# SCH_STM32_V03_2022-12-15.net
KiCad netlist of a schematic drawn in EasyEDA
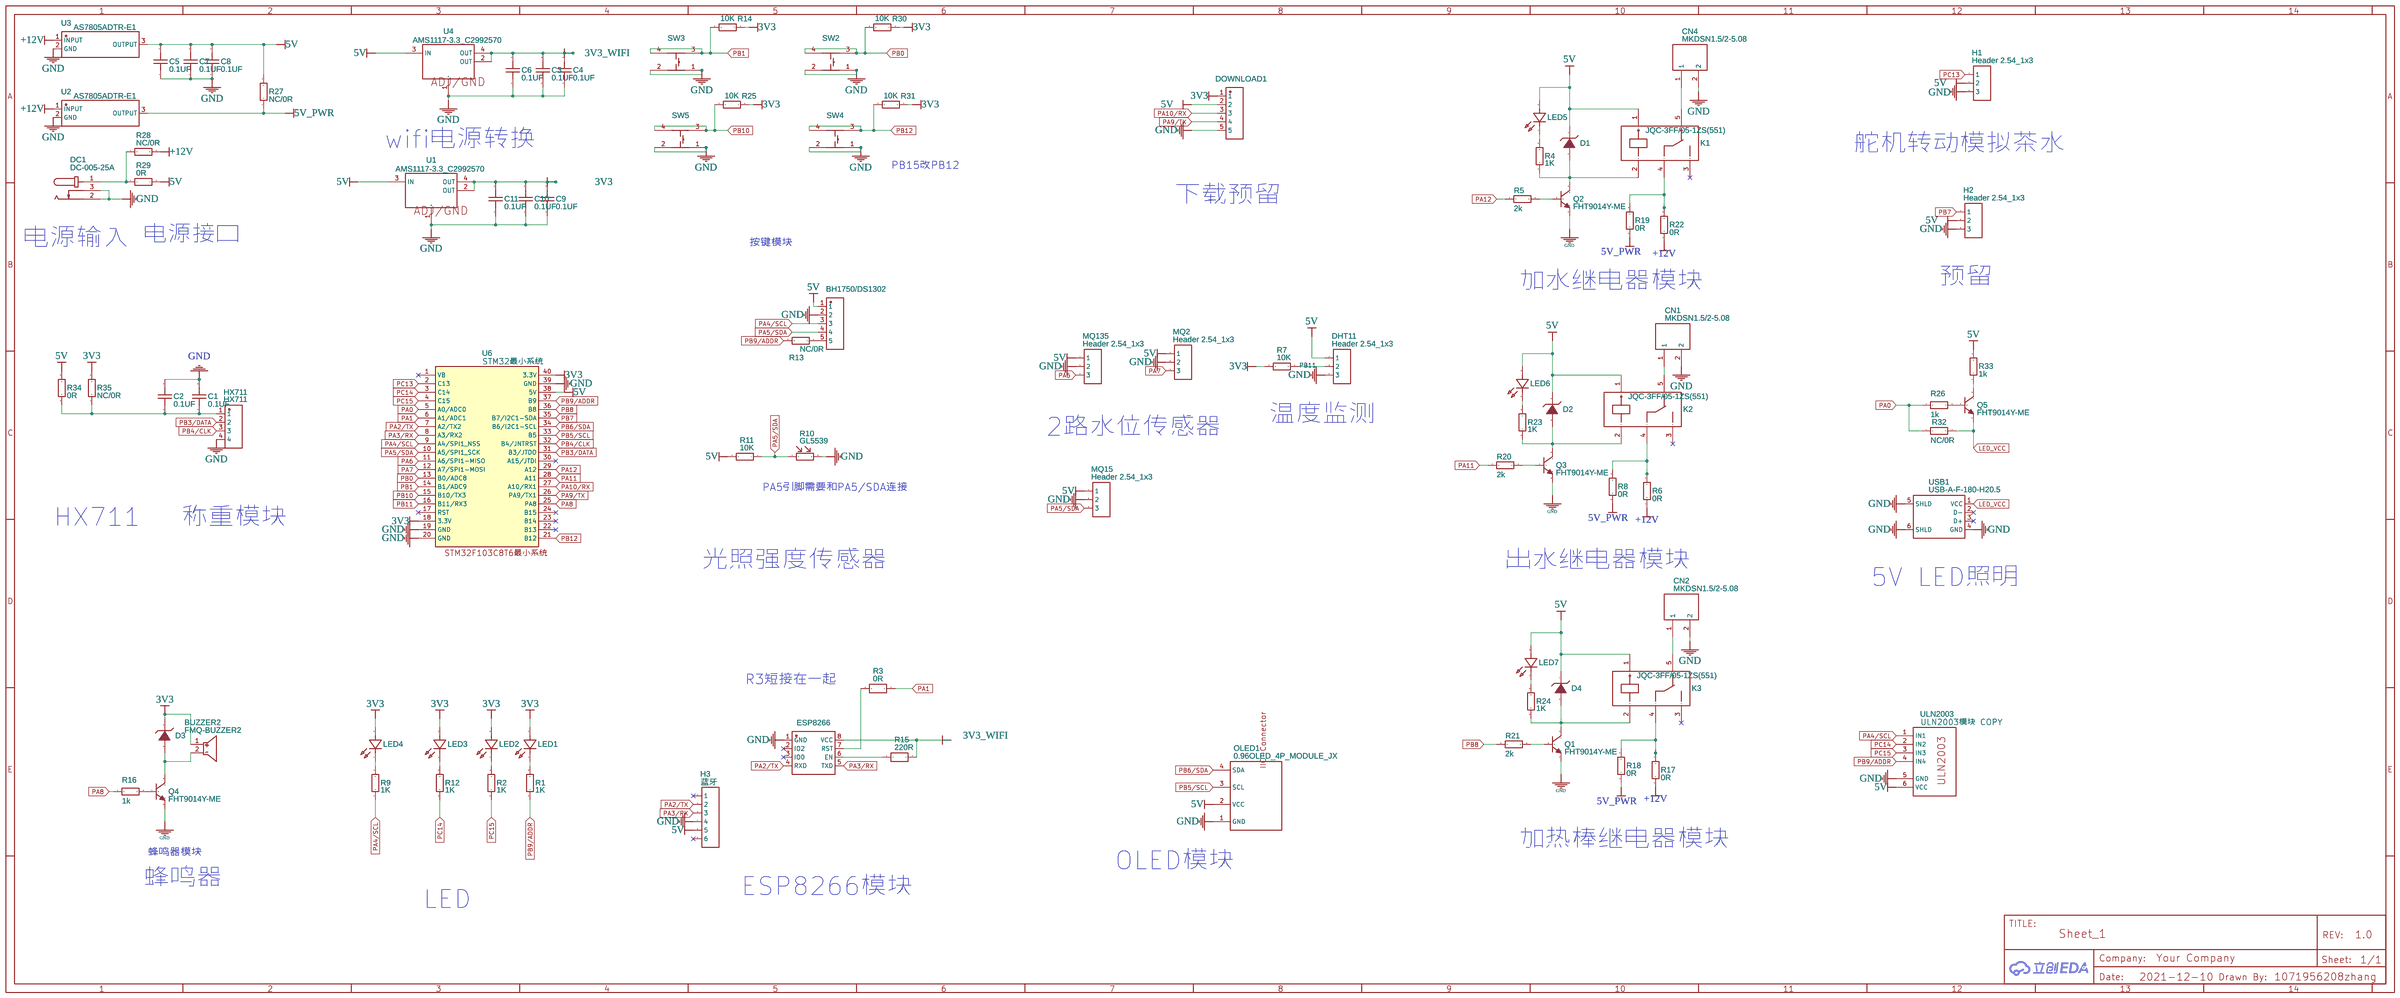
[diagram p0: schematic sheet]

(export (version "E")
  (design (tool "Eeschema 10.0.6"))
  (components
    (comp (ref "BH1750/DS1302")
      (value "Female header　2.54 1*5Ｐ")
      (fields (field (name "BOM_Supplier Part") "C46341"))
      (libsource (lib "") (part "Female header　2.54 1*5Ｐ"))
    )
    (comp (ref "BUZZER2")
      (value "FMQ-BUZZER2")
      (fields (field (name "BOM_Supplier Part") "C9900006103"))
      (libsource (lib "") (part "FMQ-BUZZER2"))
    )
    (comp (ref "C1") (value "0.1UF") (libsource (lib "") (part "C_0603_US")))
    (comp (ref "C2") (value "0.1UF") (libsource (lib "") (part "C_0603_US")))
    (comp (ref "C3") (value "0.1UF") (libsource (lib "") (part "C_0603_US")))
    (comp (ref "C4") (value "0.1UF") (libsource (lib "") (part "C_0603_US")))
    (comp (ref "C5") (value "0.1UF") (libsource (lib "") (part "C_0603_US")))
    (comp (ref "C6") (value "0.1UF") (libsource (lib "") (part "C_0603_US")))
    (comp (ref "C7") (value "0.1UF") (libsource (lib "") (part "C_0603_US")))
    (comp (ref "C8") (value "0.1UF") (libsource (lib "") (part "C_0603_US")))
    (comp (ref "C9") (value "0.1UF") (libsource (lib "") (part "C_0603_US")))
    (comp (ref "C10") (value "0.1UF") (libsource (lib "") (part "C_0603_US")))
    (comp (ref "C11") (value "0.1UF") (libsource (lib "") (part "C_0603_US")))
    (comp (ref "CN1")
      (value "MKDSN1.5/2-5.08")
      (fields (field (name "BOM_Supplier Part") "C91153"))
      (libsource (lib "") (part "MKDSN1.5/2-5.08"))
    )
    (comp (ref "CN2")
      (value "MKDSN1.5/2-5.08")
      (fields (field (name "BOM_Supplier Part") "C91153"))
      (libsource (lib "") (part "MKDSN1.5/2-5.08"))
    )
    (comp (ref "CN4")
      (value "MKDSN1.5/2-5.08")
      (fields (field (name "BOM_Supplier Part") "C91153"))
      (libsource (lib "") (part "MKDSN1.5/2-5.08"))
    )
    (comp (ref "D1")
      (value "1N4734A_C238924")
      (fields (field (name "BOM_Manufacturer Part") "1N4734A") (field (name "BOM_Supplier Part") "C238924"))
      (libsource (lib "") (part "1N4734A_C238924"))
    )
    (comp (ref "D2")
      (value "1N4734A_C238924")
      (fields (field (name "BOM_Manufacturer Part") "1N4734A") (field (name "BOM_Supplier Part") "C238924"))
      (libsource (lib "") (part "1N4734A_C238924"))
    )
    (comp (ref "D3")
      (value "1N4734A_C238924")
      (fields (field (name "BOM_Manufacturer Part") "1N4734A") (field (name "BOM_Supplier Part") "C238924"))
      (libsource (lib "") (part "1N4734A_C238924"))
    )
    (comp (ref "D4")
      (value "1N4734A_C238924")
      (fields (field (name "BOM_Manufacturer Part") "1N4734A") (field (name "BOM_Supplier Part") "C238924"))
      (libsource (lib "") (part "1N4734A_C238924"))
    )
    (comp (ref "DC1")
      (value "DC-005-25A")
      (fields (field (name "BOM_Supplier Part") "C136715"))
      (libsource (lib "") (part "DC-005-25A"))
    )
    (comp (ref "DHT11")
      (value "Header 2.54_1x3")
      (fields
        (field (name "BOM_Manufacturer Part") "Header2.54mm 1*3P")
        (field (name "BOM_Supplier Part") "C49257")
      )
      (libsource (lib "") (part "Header-Male-2.54_1x3_2"))
    )
    (comp (ref "DOWNLOAD1")
      (value "Female header　2.54 1*5Ｐ")
      (fields (field (name "BOM_Supplier Part") "C46341"))
      (libsource (lib "") (part "Female header　2.54 1*5Ｐ_1"))
    )
    (comp (ref "ESP8266")
      (value "ESP-01S_C503582")
      (fields (field (name "BOM_Manufacturer Part") "ESP-01S") (field (name "BOM_Supplier Part") "C503582"))
      (libsource (lib "") (part "ESP-01S_C503582"))
    )
    (comp (ref "H1")
      (value "Header 2.54_1x3")
      (fields
        (field (name "BOM_Manufacturer Part") "Header2.54mm 1*3P")
        (field (name "BOM_Supplier Part") "C49257")
      )
      (libsource (lib "") (part "Header-Male-2.54_1x3_1"))
    )
    (comp (ref "H2")
      (value "Header 2.54_1x3")
      (fields
        (field (name "BOM_Manufacturer Part") "Header2.54mm 1*3P")
        (field (name "BOM_Supplier Part") "C49257")
      )
      (libsource (lib "") (part "Header-Male-2.54_1x3_1"))
    )
    (comp (ref "H3")
      (value "蓝牙")
      (fields
        (field (name "BOM_Manufacturer Part") "Header-Male-2.54_1x6")
        (field (name "BOM_Supplier Part") "C37208")
      )
      (libsource (lib "") (part "Header-Male-2.54_1x6"))
    )
    (comp (ref "HX711")
      (value "HX711")
      (fields
        (field (name "BOM_Manufacturer Part") "Female header1*4P")
        (field (name "BOM_Supplier Part") "C66508")
      )
      (libsource (lib "") (part "Female header1*4P"))
    )
    (comp (ref "K1")
      (value "JQC-3FF/05-1ZS(551)")
      (fields (field (name "BOM_Supplier Part") "C9221"))
      (libsource (lib "") (part "JQC-3FF/05-1ZS(551)"))
    )
    (comp (ref "K2")
      (value "JQC-3FF/05-1ZS(551)")
      (fields (field (name "BOM_Supplier Part") "C9221"))
      (libsource (lib "") (part "JQC-3FF/05-1ZS(551)"))
    )
    (comp (ref "K3")
      (value "JQC-3FF/05-1ZS(551)")
      (fields (field (name "BOM_Supplier Part") "C9221"))
      (libsource (lib "") (part "JQC-3FF/05-1ZS(551)"))
    )
    (comp (ref "LED1")
      (value "264-7SURT/S530-A3")
      (fields (field (name "BOM_Supplier Part") "C710207"))
      (libsource (lib "") (part "264-7SURT/S530-A3"))
    )
    (comp (ref "LED2")
      (value "264-7SURT/S530-A3")
      (fields (field (name "BOM_Supplier Part") "C710207"))
      (libsource (lib "") (part "264-7SURT/S530-A3"))
    )
    (comp (ref "LED3")
      (value "264-7SURT/S530-A3")
      (fields (field (name "BOM_Supplier Part") "C710207"))
      (libsource (lib "") (part "264-7SURT/S530-A3"))
    )
    (comp (ref "LED4")
      (value "264-7SURT/S530-A3")
      (fields (field (name "BOM_Supplier Part") "C710207"))
      (libsource (lib "") (part "264-7SURT/S530-A3"))
    )
    (comp (ref "LED5")
      (value "264-7SURT/S530-A3")
      (fields (field (name "BOM_Supplier Part") "C710207"))
      (libsource (lib "") (part "264-7SURT/S530-A3"))
    )
    (comp (ref "LED6")
      (value "264-7SURT/S530-A3")
      (fields (field (name "BOM_Supplier Part") "C710207"))
      (libsource (lib "") (part "264-7SURT/S530-A3"))
    )
    (comp (ref "LED7")
      (value "264-7SURT/S530-A3")
      (fields (field (name "BOM_Supplier Part") "C710207"))
      (libsource (lib "") (part "264-7SURT/S530-A3"))
    )
    (comp (ref "MQ2")
      (value "Header 2.54_1x3")
      (fields
        (field (name "BOM_Manufacturer Part") "Header2.54mm 1*3P")
        (field (name "BOM_Supplier Part") "C49257")
      )
      (libsource (lib "") (part "Header-Male-2.54_1x3"))
    )
    (comp (ref "MQ15")
      (value "Header 2.54_1x3")
      (fields
        (field (name "BOM_Manufacturer Part") "Header2.54mm 1*3P")
        (field (name "BOM_Supplier Part") "C49257")
      )
      (libsource (lib "") (part "Header-Male-2.54_1x3"))
    )
    (comp (ref "MQ135")
      (value "Header 2.54_1x3")
      (fields
        (field (name "BOM_Manufacturer Part") "Header2.54mm 1*3P")
        (field (name "BOM_Supplier Part") "C49257")
      )
      (libsource (lib "") (part "Header-Male-2.54_1x3"))
    )
    (comp (ref "OLED1")
      (value "0.96OLED_4P_MODULE_JX")
      (fields (field (name "BOM_Supplier Part") "C9900004566"))
      (libsource (lib "") (part "0.96OLED_4P_MODULE_JX"))
    )
    (comp (ref "Q1")
      (value "FHT9014Y-ME")
      (fields (field (name "BOM_Supplier Part") "C88861"))
      (libsource (lib "") (part "FHT9014Y-ME"))
    )
    (comp (ref "Q2")
      (value "FHT9014Y-ME")
      (fields (field (name "BOM_Supplier Part") "C88861"))
      (libsource (lib "") (part "FHT9014Y-ME"))
    )
    (comp (ref "Q3")
      (value "FHT9014Y-ME")
      (fields (field (name "BOM_Supplier Part") "C88861"))
      (libsource (lib "") (part "FHT9014Y-ME"))
    )
    (comp (ref "Q4")
      (value "FHT9014Y-ME")
      (fields (field (name "BOM_Supplier Part") "C88861"))
      (libsource (lib "") (part "FHT9014Y-ME"))
    )
    (comp (ref "Q5")
      (value "FHT9014Y-ME")
      (fields (field (name "BOM_Supplier Part") "C88861"))
      (libsource (lib "") (part "FHT9014Y-ME"))
    )
    (comp (ref "R1")
      (value "1K")
      (fields
        (field (name "BOM_Manufacturer Part") "RMC08051K5%N")
        (field (name "BOM_Supplier Part") "C269727")
      )
      (libsource (lib "") (part "RMC08051K5%N"))
    )
    (comp (ref "R2")
      (value "1K")
      (fields
        (field (name "BOM_Manufacturer Part") "RMC08051K5%N")
        (field (name "BOM_Supplier Part") "C269727")
      )
      (libsource (lib "") (part "RMC08051K5%N"))
    )
    (comp (ref "R3") (value "0R") (libsource (lib "") (part "R_0603_EU")))
    (comp (ref "R4")
      (value "1K")
      (fields
        (field (name "BOM_Manufacturer Part") "RMC08051K5%N")
        (field (name "BOM_Supplier Part") "C269727")
      )
      (libsource (lib "") (part "RMC08051K5%N"))
    )
    (comp (ref "R5")
      (value "2k")
      (fields
        (field (name "BOM_Manufacturer Part") "RMC08051K5%N")
        (field (name "BOM_Supplier Part") "C269727")
      )
      (libsource (lib "") (part "RMC08051K5%N_1"))
    )
    (comp (ref "R6")
      (value "0R")
      (fields
        (field (name "BOM_Manufacturer Part") "RMC08051K5%N")
        (field (name "BOM_Supplier Part") "C269727")
      )
      (libsource (lib "") (part "RMC08051K5%N"))
    )
    (comp (ref "R7")
      (value "10K")
      (fields
        (field (name "BOM_Manufacturer Part") "RMC08051K5%N")
        (field (name "BOM_Supplier Part") "C269727")
      )
      (libsource (lib "") (part "RMC08051K5%N_2"))
    )
    (comp (ref "R8")
      (value "0R")
      (fields
        (field (name "BOM_Manufacturer Part") "RMC08051K5%N")
        (field (name "BOM_Supplier Part") "C269727")
      )
      (libsource (lib "") (part "RMC08051K5%N"))
    )
    (comp (ref "R9")
      (value "1K")
      (fields
        (field (name "BOM_Manufacturer Part") "RMC08051K5%N")
        (field (name "BOM_Supplier Part") "C269727")
      )
      (libsource (lib "") (part "RMC08051K5%N"))
    )
    (comp (ref "R10")
      (value "GL5539")
      (fields (field (name "BOM_Supplier Part") "C125630"))
      (libsource (lib "") (part "GL5539"))
    )
    (comp (ref "R11")
      (value "10K")
      (fields
        (field (name "BOM_Manufacturer Part") "RMC08051K5%N")
        (field (name "BOM_Supplier Part") "C269727")
      )
      (libsource (lib "") (part "RMC08051K5%N_2"))
    )
    (comp (ref "R12")
      (value "1K")
      (fields
        (field (name "BOM_Manufacturer Part") "RMC08051K5%N")
        (field (name "BOM_Supplier Part") "C269727")
      )
      (libsource (lib "") (part "RMC08051K5%N"))
    )
    (comp (ref "R13")
      (value "NC/0R")
      (fields
        (field (name "BOM_Manufacturer Part") "RMC08051K5%N")
        (field (name "BOM_Supplier Part") "C269727")
      )
      (libsource (lib "") (part "RMC08051K5%N_2"))
    )
    (comp (ref "R14")
      (value "10K")
      (fields
        (field (name "BOM_Manufacturer Part") "RMC08051K5%N")
        (field (name "BOM_Supplier Part") "C269727")
      )
      (libsource (lib "") (part "RMC08051K5%N_2"))
    )
    (comp (ref "R15") (value "220R") (libsource (lib "") (part "R_0603_EU")))
    (comp (ref "R16")
      (value "1k")
      (fields
        (field (name "BOM_Manufacturer Part") "RMC08051K5%N")
        (field (name "BOM_Supplier Part") "C269727")
      )
      (libsource (lib "") (part "RMC08051K5%N_1"))
    )
    (comp (ref "R17")
      (value "0R")
      (fields
        (field (name "BOM_Manufacturer Part") "RMC08051K5%N")
        (field (name "BOM_Supplier Part") "C269727")
      )
      (libsource (lib "") (part "RMC08051K5%N"))
    )
    (comp (ref "R18")
      (value "0R")
      (fields
        (field (name "BOM_Manufacturer Part") "RMC08051K5%N")
        (field (name "BOM_Supplier Part") "C269727")
      )
      (libsource (lib "") (part "RMC08051K5%N"))
    )
    (comp (ref "R19")
      (value "0R")
      (fields
        (field (name "BOM_Manufacturer Part") "RMC08051K5%N")
        (field (name "BOM_Supplier Part") "C269727")
      )
      (libsource (lib "") (part "RMC08051K5%N"))
    )
    (comp (ref "R20")
      (value "2k")
      (fields
        (field (name "BOM_Manufacturer Part") "RMC08051K5%N")
        (field (name "BOM_Supplier Part") "C269727")
      )
      (libsource (lib "") (part "RMC08051K5%N_1"))
    )
    (comp (ref "R21")
      (value "2k")
      (fields
        (field (name "BOM_Manufacturer Part") "RMC08051K5%N")
        (field (name "BOM_Supplier Part") "C269727")
      )
      (libsource (lib "") (part "RMC08051K5%N_1"))
    )
    (comp (ref "R22")
      (value "0R")
      (fields
        (field (name "BOM_Manufacturer Part") "RMC08051K5%N")
        (field (name "BOM_Supplier Part") "C269727")
      )
      (libsource (lib "") (part "RMC08051K5%N"))
    )
    (comp (ref "R23")
      (value "1K")
      (fields
        (field (name "BOM_Manufacturer Part") "RMC08051K5%N")
        (field (name "BOM_Supplier Part") "C269727")
      )
      (libsource (lib "") (part "RMC08051K5%N"))
    )
    (comp (ref "R24")
      (value "1K")
      (fields
        (field (name "BOM_Manufacturer Part") "RMC08051K5%N")
        (field (name "BOM_Supplier Part") "C269727")
      )
      (libsource (lib "") (part "RMC08051K5%N"))
    )
    (comp (ref "R25")
      (value "10K")
      (fields
        (field (name "BOM_Manufacturer Part") "RMC08051K5%N")
        (field (name "BOM_Supplier Part") "C269727")
      )
      (libsource (lib "") (part "RMC08051K5%N_2"))
    )
    (comp (ref "R26")
      (value "1k")
      (fields
        (field (name "BOM_Manufacturer Part") "RMC08051K5%N")
        (field (name "BOM_Supplier Part") "C269727")
      )
      (libsource (lib "") (part "RMC08051K5%N_1"))
    )
    (comp (ref "R27")
      (value "NC/0R")
      (fields
        (field (name "BOM_Manufacturer Part") "RMC08051K5%N")
        (field (name "BOM_Supplier Part") "C269727")
      )
      (libsource (lib "") (part "RMC08051K5%N"))
    )
    (comp (ref "R28")
      (value "NC/0R")
      (fields
        (field (name "BOM_Manufacturer Part") "RMC08051K5%N")
        (field (name "BOM_Supplier Part") "C269727")
      )
      (libsource (lib "") (part "RMC08051K5%N_1"))
    )
    (comp (ref "R29")
      (value "0R")
      (fields
        (field (name "BOM_Manufacturer Part") "RMC08051K5%N")
        (field (name "BOM_Supplier Part") "C269727")
      )
      (libsource (lib "") (part "RMC08051K5%N_1"))
    )
    (comp (ref "R30")
      (value "10K")
      (fields
        (field (name "BOM_Manufacturer Part") "RMC08051K5%N")
        (field (name "BOM_Supplier Part") "C269727")
      )
      (libsource (lib "") (part "RMC08051K5%N_2"))
    )
    (comp (ref "R31")
      (value "10K")
      (fields
        (field (name "BOM_Manufacturer Part") "RMC08051K5%N")
        (field (name "BOM_Supplier Part") "C269727")
      )
      (libsource (lib "") (part "RMC08051K5%N_2"))
    )
    (comp (ref "R32")
      (value "NC/0R")
      (fields
        (field (name "BOM_Manufacturer Part") "RMC08051K5%N")
        (field (name "BOM_Supplier Part") "C269727")
      )
      (libsource (lib "") (part "RMC08051K5%N_1"))
    )
    (comp (ref "R33")
      (value "1k")
      (fields
        (field (name "BOM_Manufacturer Part") "RMC08051K5%N")
        (field (name "BOM_Supplier Part") "C269727")
      )
      (libsource (lib "") (part "RMC08051K5%N"))
    )
    (comp (ref "R34")
      (value "0R")
      (fields
        (field (name "BOM_Manufacturer Part") "RMC08051K5%N")
        (field (name "BOM_Supplier Part") "C269727")
      )
      (libsource (lib "") (part "RMC08051K5%N"))
    )
    (comp (ref "R35")
      (value "NC/0R")
      (fields
        (field (name "BOM_Manufacturer Part") "RMC08051K5%N")
        (field (name "BOM_Supplier Part") "C269727")
      )
      (libsource (lib "") (part "RMC08051K5%N"))
    )
    (comp (ref "SW2")
      (value "K2-1102DP-A4SW-04")
      (fields (field (name "BOM_Supplier Part") "C223769"))
      (libsource (lib "") (part "K2-1102DP-A4SW-04"))
    )
    (comp (ref "SW3")
      (value "K2-1102DP-A4SW-04")
      (fields (field (name "BOM_Supplier Part") "C223769"))
      (libsource (lib "") (part "K2-1102DP-A4SW-04"))
    )
    (comp (ref "SW4")
      (value "K2-1102DP-A4SW-04")
      (fields (field (name "BOM_Supplier Part") "C223769"))
      (libsource (lib "") (part "K2-1102DP-A4SW-04"))
    )
    (comp (ref "SW5")
      (value "K2-1102DP-A4SW-04")
      (fields (field (name "BOM_Supplier Part") "C223769"))
      (libsource (lib "") (part "K2-1102DP-A4SW-04"))
    )
    (comp (ref "U1")
      (value "AMS1117-3.3_C2992570")
      (fields
        (field (name "BOM_Manufacturer Part") "AMS1117-3.3")
        (field (name "BOM_Supplier Part") "C2992570")
      )
      (libsource (lib "") (part "AMS1117-3.3_C2992570"))
    )
    (comp (ref "U2")
      (value "AS7805ADTR-E1")
      (fields (field (name "BOM_Supplier Part") "C127926"))
      (libsource (lib "") (part "AS7805ADTR-E1"))
    )
    (comp (ref "U3")
      (value "AS7805ADTR-E1")
      (fields (field (name "BOM_Supplier Part") "C127926"))
      (libsource (lib "") (part "AS7805ADTR-E1"))
    )
    (comp (ref "U4")
      (value "AMS1117-3.3_C2992570")
      (fields
        (field (name "BOM_Manufacturer Part") "AMS1117-3.3")
        (field (name "BOM_Supplier Part") "C2992570")
      )
      (libsource (lib "") (part "AMS1117-3.3_C2992570"))
    )
    (comp (ref "U6") (value "STM32最小系统") (libsource (lib "") (part "STM32最小系统")))
    (comp (ref "ULN2003") (value "ULN2003模块 COPY") (libsource (lib "") (part "ULN2003模块")))
    (comp (ref "USB1")
      (value "USB-A-F-180-H20.5")
      (fields
        (field (name "BOM_Manufacturer Part") "916-151A101DY10200")
        (field (name "BOM_Supplier Part") "C168710")
      )
      (libsource (lib "") (part "USB-A-F-180-H20.5"))
    )
  )
  (nets
    (net (code "1") (name "+12V") (class "Default")
      (node (ref "R17") (pin "1") (pinfunction "1_1") (pintype "unspecified"))
      (node (ref "R22") (pin "1") (pinfunction "1_1") (pintype "unspecified"))
      (node (ref "R28") (pin "2") (pinfunction "2_2") (pintype "unspecified"))
      (node (ref "R6") (pin "1") (pinfunction "1_1") (pintype "unspecified"))
      (node (ref "U2") (pin "1") (pinfunction "INPUT_1") (pintype "unspecified"))
      (node (ref "U3") (pin "1") (pinfunction "INPUT_1") (pintype "unspecified"))
    )
    (net (code "2") (name "3V3") (class "Default")
      (node (ref "BUZZER2") (pin "1") (pinfunction "1_1") (pintype "unspecified"))
      (node (ref "C10") (pin "2") (pinfunction "2_2") (pintype "unspecified"))
      (node (ref "C11") (pin "2") (pinfunction "2_2") (pintype "unspecified"))
      (node (ref "C9") (pin "2") (pinfunction "2_2") (pintype "unspecified"))
      (node (ref "D3") (pin "1") (pinfunction "K_1") (pintype "unspecified"))
      (node (ref "DOWNLOAD1") (pin "1") (pinfunction "1_1") (pintype "unspecified"))
      (node (ref "LED1") (pin "2") (pinfunction "+_2") (pintype "unspecified"))
      (node (ref "LED2") (pin "2") (pinfunction "+_2") (pintype "unspecified"))
      (node (ref "LED3") (pin "2") (pinfunction "+_2") (pintype "unspecified"))
      (node (ref "LED4") (pin "2") (pinfunction "+_2") (pintype "unspecified"))
      (node (ref "R14") (pin "1") (pinfunction "1_1") (pintype "unspecified"))
      (node (ref "R25") (pin "1") (pinfunction "1_1") (pintype "unspecified"))
      (node (ref "R30") (pin "1") (pinfunction "1_1") (pintype "unspecified"))
      (node (ref "R31") (pin "1") (pinfunction "1_1") (pintype "unspecified"))
      (node (ref "R35") (pin "2") (pinfunction "2_2") (pintype "unspecified"))
      (node (ref "R7") (pin "2") (pinfunction "2_2") (pintype "unspecified"))
      (node (ref "U1") (pin "2") (pinfunction "OUT_2") (pintype "passive"))
      (node (ref "U1") (pin "4") (pinfunction "OUT_4") (pintype "passive"))
      (node (ref "U6") (pin "18") (pinfunction "3.3V_18") (pintype "bidirectional"))
      (node (ref "U6") (pin "40") (pinfunction "3.3V_40") (pintype "unspecified"))
    )
    (net (code "3") (name "3V3_WIFI") (class "Default")
      (node (ref "C3") (pin "2") (pinfunction "2_2") (pintype "unspecified"))
      (node (ref "C4") (pin "2") (pinfunction "2_2") (pintype "unspecified"))
      (node (ref "C6") (pin "2") (pinfunction "2_2") (pintype "unspecified"))
      (node (ref "ESP8266") (pin "8") (pinfunction "VCC_8") (pintype "unspecified"))
      (node (ref "R15") (pin "1") (pinfunction "1_1") (pintype "unspecified"))
      (node (ref "U4") (pin "2") (pinfunction "OUT_2") (pintype "passive"))
      (node (ref "U4") (pin "4") (pinfunction "OUT_4") (pintype "passive"))
    )
    (net (code "4") (name "5V") (class "Default")
      (node (ref "BH1750/DS1302") (pin "1") (pinfunction "1_1") (pintype "unspecified"))
      (node (ref "C5") (pin "2") (pinfunction "2_2") (pintype "unspecified"))
      (node (ref "C7") (pin "2") (pinfunction "2_2") (pintype "unspecified"))
      (node (ref "C8") (pin "2") (pinfunction "2_2") (pintype "unspecified"))
      (node (ref "D1") (pin "1") (pinfunction "K_1") (pintype "unspecified"))
      (node (ref "D2") (pin "1") (pinfunction "K_1") (pintype "unspecified"))
      (node (ref "D4") (pin "1") (pinfunction "K_1") (pintype "unspecified"))
      (node (ref "DHT11") (pin "1") (pinfunction "1_1") (pintype "input"))
      (node (ref "DOWNLOAD1") (pin "2") (pinfunction "2_2") (pintype "unspecified"))
      (node (ref "H1") (pin "2") (pinfunction "2_2") (pintype "input"))
      (node (ref "H2") (pin "2") (pinfunction "2_2") (pintype "input"))
      (node (ref "H3") (pin "5") (pinfunction "5_5") (pintype "input"))
      (node (ref "K1") (pin "1") (pinfunction "1_1") (pintype "input"))
      (node (ref "K2") (pin "1") (pinfunction "1_1") (pintype "input"))
      (node (ref "K3") (pin "1") (pinfunction "1_1") (pintype "input"))
      (node (ref "LED5") (pin "2") (pinfunction "+_2") (pintype "unspecified"))
      (node (ref "LED6") (pin "2") (pinfunction "+_2") (pintype "unspecified"))
      (node (ref "LED7") (pin "2") (pinfunction "+_2") (pintype "unspecified"))
      (node (ref "MQ135") (pin "1") (pinfunction "1_1") (pintype "input"))
      (node (ref "MQ15") (pin "1") (pinfunction "1_1") (pintype "input"))
      (node (ref "MQ2") (pin "1") (pinfunction "1_1") (pintype "input"))
      (node (ref "OLED1") (pin "2") (pinfunction "VCC_2") (pintype "unspecified"))
      (node (ref "R11") (pin "2") (pinfunction "2_2") (pintype "unspecified"))
      (node (ref "R27") (pin "2") (pinfunction "2_2") (pintype "unspecified"))
      (node (ref "R29") (pin "2") (pinfunction "2_2") (pintype "unspecified"))
      (node (ref "R33") (pin "2") (pinfunction "2_2") (pintype "unspecified"))
      (node (ref "R34") (pin "2") (pinfunction "2_2") (pintype "unspecified"))
      (node (ref "U1") (pin "3") (pinfunction "IN_3") (pintype "passive"))
      (node (ref "U3") (pin "3") (pinfunction "OUTPUT_3") (pintype "unspecified"))
      (node (ref "U4") (pin "3") (pinfunction "IN_3") (pintype "passive"))
      (node (ref "U6") (pin "38") (pinfunction "5V_38") (pintype "unspecified"))
      (node (ref "ULN2003") (pin "6") (pinfunction "VCC_6") (pintype "unspecified"))
    )
    (net (code "5") (name "5V_PWR") (class "Default")
      (node (ref "R18") (pin "1") (pinfunction "1_1") (pintype "unspecified"))
      (node (ref "R19") (pin "1") (pinfunction "1_1") (pintype "unspecified"))
      (node (ref "R27") (pin "1") (pinfunction "1_1") (pintype "unspecified"))
      (node (ref "R8") (pin "1") (pinfunction "1_1") (pintype "unspecified"))
      (node (ref "U2") (pin "3") (pinfunction "OUTPUT_3") (pintype "unspecified"))
    )
    (net (code "6") (name "GND") (class "Default")
      (node (ref "BH1750/DS1302") (pin "2") (pinfunction "2_2") (pintype "unspecified"))
      (node (ref "C1") (pin "2") (pinfunction "2_2") (pintype "unspecified"))
      (node (ref "C10") (pin "1") (pinfunction "1_1") (pintype "unspecified"))
      (node (ref "C11") (pin "1") (pinfunction "1_1") (pintype "unspecified"))
      (node (ref "C2") (pin "2") (pinfunction "2_2") (pintype "unspecified"))
      (node (ref "C3") (pin "1") (pinfunction "1_1") (pintype "unspecified"))
      (node (ref "C4") (pin "1") (pinfunction "1_1") (pintype "unspecified"))
      (node (ref "C5") (pin "1") (pinfunction "1_1") (pintype "unspecified"))
      (node (ref "C6") (pin "1") (pinfunction "1_1") (pintype "unspecified"))
      (node (ref "C7") (pin "1") (pinfunction "1_1") (pintype "unspecified"))
      (node (ref "C8") (pin "1") (pinfunction "1_1") (pintype "unspecified"))
      (node (ref "C9") (pin "1") (pinfunction "1_1") (pintype "unspecified"))
      (node (ref "CN1") (pin "2") (pinfunction "2_2") (pintype "unspecified"))
      (node (ref "CN2") (pin "2") (pinfunction "2_2") (pintype "unspecified"))
      (node (ref "CN4") (pin "2") (pinfunction "2_2") (pintype "unspecified"))
      (node (ref "DC1") (pin "2") (pinfunction "2_2") (pintype "unspecified"))
      (node (ref "DC1") (pin "3") (pinfunction "3_3") (pintype "unspecified"))
      (node (ref "DHT11") (pin "3") (pinfunction "3_3") (pintype "input"))
      (node (ref "DOWNLOAD1") (pin "5") (pinfunction "5_5") (pintype "unspecified"))
      (node (ref "ESP8266") (pin "1") (pinfunction "GND_1") (pintype "unspecified"))
      (node (ref "H1") (pin "3") (pinfunction "3_3") (pintype "input"))
      (node (ref "H2") (pin "3") (pinfunction "3_3") (pintype "input"))
      (node (ref "H3") (pin "4") (pinfunction "4_4") (pintype "input"))
      (node (ref "HX711") (pin "4") (pinfunction "4_4") (pintype "unspecified"))
      (node (ref "MQ135") (pin "2") (pinfunction "2_2") (pintype "input"))
      (node (ref "MQ15") (pin "2") (pinfunction "2_2") (pintype "input"))
      (node (ref "MQ2") (pin "2") (pinfunction "2_2") (pintype "input"))
      (node (ref "OLED1") (pin "1") (pinfunction "GND_1") (pintype "unspecified"))
      (node (ref "Q1") (pin "2") (pinfunction "E_2") (pintype "unspecified"))
      (node (ref "Q2") (pin "2") (pinfunction "E_2") (pintype "unspecified"))
      (node (ref "Q3") (pin "2") (pinfunction "E_2") (pintype "unspecified"))
      (node (ref "Q4") (pin "2") (pinfunction "E_2") (pintype "unspecified"))
      (node (ref "R10") (pin "2") (pinfunction "2_2") (pintype "input"))
      (node (ref "SW2") (pin "1") (pinfunction "1_1") (pintype "unspecified"))
      (node (ref "SW2") (pin "2") (pinfunction "2_2") (pintype "unspecified"))
      (node (ref "SW3") (pin "1") (pinfunction "1_1") (pintype "unspecified"))
      (node (ref "SW3") (pin "2") (pinfunction "2_2") (pintype "unspecified"))
      (node (ref "SW4") (pin "1") (pinfunction "1_1") (pintype "unspecified"))
      (node (ref "SW4") (pin "2") (pinfunction "2_2") (pintype "unspecified"))
      (node (ref "SW5") (pin "1") (pinfunction "1_1") (pintype "unspecified"))
      (node (ref "SW5") (pin "2") (pinfunction "2_2") (pintype "unspecified"))
      (node (ref "U1") (pin "1") (pinfunction "ADJ/GND_1") (pintype "passive"))
      (node (ref "U2") (pin "2") (pinfunction "GND_2") (pintype "unspecified"))
      (node (ref "U3") (pin "2") (pinfunction "GND_2") (pintype "unspecified"))
      (node (ref "U4") (pin "1") (pinfunction "ADJ/GND_1") (pintype "passive"))
      (node (ref "U6") (pin "19") (pinfunction "GND_19") (pintype "bidirectional"))
      (node (ref "U6") (pin "20") (pinfunction "GND_20") (pintype "bidirectional"))
      (node (ref "U6") (pin "39") (pinfunction "GND_39") (pintype "unspecified"))
      (node (ref "ULN2003") (pin "5") (pinfunction "GND_5") (pintype "unspecified"))
      (node (ref "USB1") (pin "4") (pinfunction "GND_4") (pintype "input"))
      (node (ref "USB1") (pin "5") (pinfunction "SHLD_5") (pintype "unspecified"))
      (node (ref "USB1") (pin "6") (pinfunction "SHLD_6") (pintype "unspecified"))
    )
    (net (code "7") (name "LED_VCC") (class "Default")
      (node (ref "Q5") (pin "2") (pinfunction "E_2") (pintype "unspecified"))
      (node (ref "R32") (pin "2") (pinfunction "2_2") (pintype "unspecified"))
      (node (ref "USB1") (pin "1") (pinfunction "VCC_1") (pintype "input"))
    )
    (net (code "8") (name "Net-(BH1750/DS1302-Pad5)") (class "Default")
      (node (ref "BH1750/DS1302") (pin "5") (pinfunction "5_5") (pintype "unspecified"))
      (node (ref "R13") (pin "1") (pinfunction "1_1") (pintype "unspecified"))
    )
    (net (code "9") (name "Net-(C1-Pad1)") (class "Default")
      (node (ref "C1") (pin "1") (pinfunction "1_1") (pintype "unspecified"))
      (node (ref "C2") (pin "1") (pinfunction "1_1") (pintype "unspecified"))
      (node (ref "HX711") (pin "1") (pinfunction "1_1") (pintype "unspecified"))
      (node (ref "R34") (pin "1") (pinfunction "1_1") (pintype "unspecified"))
      (node (ref "R35") (pin "1") (pinfunction "1_1") (pintype "unspecified"))
    )
    (net (code "10") (name "Net-(CN1-Pad1)") (class "Default")
      (node (ref "CN1") (pin "1") (pinfunction "1_1") (pintype "unspecified"))
      (node (ref "K2") (pin "5") (pinfunction "5_5") (pintype "input"))
    )
    (net (code "11") (name "Net-(CN2-Pad1)") (class "Default")
      (node (ref "CN2") (pin "1") (pinfunction "1_1") (pintype "unspecified"))
      (node (ref "K3") (pin "5") (pinfunction "5_5") (pintype "input"))
    )
    (net (code "12") (name "Net-(CN4-Pad1)") (class "Default")
      (node (ref "CN4") (pin "1") (pinfunction "1_1") (pintype "unspecified"))
      (node (ref "K1") (pin "5") (pinfunction "5_5") (pintype "input"))
    )
    (net (code "13") (name "Net-(D1-A)") (class "Default")
      (node (ref "D1") (pin "2") (pinfunction "A_2") (pintype "unspecified"))
      (node (ref "K1") (pin "2") (pinfunction "2_2") (pintype "input"))
      (node (ref "Q2") (pin "3") (pinfunction "C_3") (pintype "unspecified"))
      (node (ref "R4") (pin "1") (pinfunction "1_1") (pintype "unspecified"))
    )
    (net (code "14") (name "Net-(D2-A)") (class "Default")
      (node (ref "D2") (pin "2") (pinfunction "A_2") (pintype "unspecified"))
      (node (ref "K2") (pin "2") (pinfunction "2_2") (pintype "input"))
      (node (ref "Q3") (pin "3") (pinfunction "C_3") (pintype "unspecified"))
      (node (ref "R23") (pin "1") (pinfunction "1_1") (pintype "unspecified"))
    )
    (net (code "15") (name "Net-(D3-A)") (class "Default")
      (node (ref "BUZZER2") (pin "2") (pinfunction "2_2") (pintype "unspecified"))
      (node (ref "D3") (pin "2") (pinfunction "A_2") (pintype "unspecified"))
      (node (ref "Q4") (pin "3") (pinfunction "C_3") (pintype "unspecified"))
    )
    (net (code "16") (name "Net-(D4-A)") (class "Default")
      (node (ref "D4") (pin "2") (pinfunction "A_2") (pintype "unspecified"))
      (node (ref "K3") (pin "2") (pinfunction "2_2") (pintype "input"))
      (node (ref "Q1") (pin "3") (pinfunction "C_3") (pintype "unspecified"))
      (node (ref "R24") (pin "1") (pinfunction "1_1") (pintype "unspecified"))
    )
    (net (code "17") (name "Net-(DC1-Pad1)") (class "Default")
      (node (ref "DC1") (pin "1") (pinfunction "1_1") (pintype "unspecified"))
      (node (ref "R28") (pin "1") (pinfunction "1_1") (pintype "unspecified"))
      (node (ref "R29") (pin "1") (pinfunction "1_1") (pintype "unspecified"))
    )
    (net (code "18") (name "Net-(ESP8266-EN)") (class "Default")
      (node (ref "ESP8266") (pin "6") (pinfunction "EN_6") (pintype "unspecified"))
      (node (ref "R15") (pin "2") (pinfunction "2_2") (pintype "unspecified"))
    )
    (net (code "19") (name "Net-(ESP8266-RST)") (class "Default")
      (node (ref "ESP8266") (pin "7") (pinfunction "RST_7") (pintype "unspecified"))
      (node (ref "R3") (pin "2") (pinfunction "2_2") (pintype "unspecified"))
    )
    (net (code "20") (name "Net-(K1-Pad4)") (class "Default")
      (node (ref "K1") (pin "4") (pinfunction "4_4") (pintype "input"))
      (node (ref "R19") (pin "2") (pinfunction "2_2") (pintype "unspecified"))
      (node (ref "R22") (pin "2") (pinfunction "2_2") (pintype "unspecified"))
    )
    (net (code "21") (name "Net-(K2-Pad4)") (class "Default")
      (node (ref "K2") (pin "4") (pinfunction "4_4") (pintype "input"))
      (node (ref "R6") (pin "2") (pinfunction "2_2") (pintype "unspecified"))
      (node (ref "R8") (pin "2") (pinfunction "2_2") (pintype "unspecified"))
    )
    (net (code "22") (name "Net-(K3-Pad4)") (class "Default")
      (node (ref "K3") (pin "4") (pinfunction "4_4") (pintype "input"))
      (node (ref "R17") (pin "2") (pinfunction "2_2") (pintype "unspecified"))
      (node (ref "R18") (pin "2") (pinfunction "2_2") (pintype "unspecified"))
    )
    (net (code "23") (name "Net-(LED1--)") (class "Default")
      (node (ref "LED1") (pin "1") (pinfunction "-_1") (pintype "unspecified"))
      (node (ref "R1") (pin "2") (pinfunction "2_2") (pintype "unspecified"))
    )
    (net (code "24") (name "Net-(LED2--)") (class "Default")
      (node (ref "LED2") (pin "1") (pinfunction "-_1") (pintype "unspecified"))
      (node (ref "R2") (pin "2") (pinfunction "2_2") (pintype "unspecified"))
    )
    (net (code "25") (name "Net-(LED3--)") (class "Default")
      (node (ref "LED3") (pin "1") (pinfunction "-_1") (pintype "unspecified"))
      (node (ref "R12") (pin "2") (pinfunction "2_2") (pintype "unspecified"))
    )
    (net (code "26") (name "Net-(LED4--)") (class "Default")
      (node (ref "LED4") (pin "1") (pinfunction "-_1") (pintype "unspecified"))
      (node (ref "R9") (pin "2") (pinfunction "2_2") (pintype "unspecified"))
    )
    (net (code "27") (name "Net-(LED5--)") (class "Default")
      (node (ref "LED5") (pin "1") (pinfunction "-_1") (pintype "unspecified"))
      (node (ref "R4") (pin "2") (pinfunction "2_2") (pintype "unspecified"))
    )
    (net (code "28") (name "Net-(LED6--)") (class "Default")
      (node (ref "LED6") (pin "1") (pinfunction "-_1") (pintype "unspecified"))
      (node (ref "R23") (pin "2") (pinfunction "2_2") (pintype "unspecified"))
    )
    (net (code "29") (name "Net-(LED7--)") (class "Default")
      (node (ref "LED7") (pin "1") (pinfunction "-_1") (pintype "unspecified"))
      (node (ref "R24") (pin "2") (pinfunction "2_2") (pintype "unspecified"))
    )
    (net (code "30") (name "Net-(Q1-B)") (class "Default")
      (node (ref "Q1") (pin "1") (pinfunction "B_1") (pintype "unspecified"))
      (node (ref "R21") (pin "2") (pinfunction "2_2") (pintype "unspecified"))
    )
    (net (code "31") (name "Net-(Q2-B)") (class "Default")
      (node (ref "Q2") (pin "1") (pinfunction "B_1") (pintype "unspecified"))
      (node (ref "R5") (pin "2") (pinfunction "2_2") (pintype "unspecified"))
    )
    (net (code "32") (name "Net-(Q3-B)") (class "Default")
      (node (ref "Q3") (pin "1") (pinfunction "B_1") (pintype "unspecified"))
      (node (ref "R20") (pin "2") (pinfunction "2_2") (pintype "unspecified"))
    )
    (net (code "33") (name "Net-(Q4-B)") (class "Default")
      (node (ref "Q4") (pin "1") (pinfunction "B_1") (pintype "unspecified"))
      (node (ref "R16") (pin "2") (pinfunction "2_2") (pintype "unspecified"))
    )
    (net (code "34") (name "Net-(Q5-B)") (class "Default")
      (node (ref "Q5") (pin "1") (pinfunction "B_1") (pintype "unspecified"))
      (node (ref "R26") (pin "2") (pinfunction "2_2") (pintype "unspecified"))
    )
    (net (code "35") (name "Net-(Q5-C)") (class "Default")
      (node (ref "Q5") (pin "3") (pinfunction "C_3") (pintype "unspecified"))
      (node (ref "R33") (pin "1") (pinfunction "1_1") (pintype "unspecified"))
    )
    (net (code "36") (name "PA0") (class "Default")
      (node (ref "R26") (pin "1") (pinfunction "1_1") (pintype "unspecified"))
      (node (ref "R32") (pin "1") (pinfunction "1_1") (pintype "unspecified"))
      (node (ref "U6") (pin "5") (pinfunction "A0/ADC0_5") (pintype "bidirectional"))
    )
    (net (code "37") (name "PA1") (class "Default")
      (node (ref "R3") (pin "1") (pinfunction "1_1") (pintype "unspecified"))
      (node (ref "U6") (pin "6") (pinfunction "A1/ADC1_6") (pintype "bidirectional"))
    )
    (net (code "38") (name "PA2{slash}TX") (class "Default")
      (node (ref "ESP8266") (pin "4") (pinfunction "RXD_4") (pintype "unspecified"))
      (node (ref "H3") (pin "2") (pinfunction "2_2") (pintype "input"))
      (node (ref "U6") (pin "7") (pinfunction "A2/TX2_7") (pintype "bidirectional"))
    )
    (net (code "39") (name "PA3{slash}RX") (class "Default")
      (node (ref "ESP8266") (pin "5") (pinfunction "TXD_5") (pintype "unspecified"))
      (node (ref "H3") (pin "3") (pinfunction "3_3") (pintype "input"))
      (node (ref "U6") (pin "8") (pinfunction "A3/RX2_8") (pintype "bidirectional"))
    )
    (net (code "40") (name "PA4{slash}SCL") (class "Default")
      (node (ref "BH1750/DS1302") (pin "3") (pinfunction "3_3") (pintype "unspecified"))
      (node (ref "R9") (pin "1") (pinfunction "1_1") (pintype "unspecified"))
      (node (ref "U6") (pin "9") (pinfunction "A4/SPI1_NSS_9") (pintype "bidirectional"))
      (node (ref "ULN2003") (pin "1") (pinfunction "IN1_1") (pintype "unspecified"))
    )
    (net (code "41") (name "PA5{slash}SDA") (class "Default")
      (node (ref "BH1750/DS1302") (pin "4") (pinfunction "4_4") (pintype "unspecified"))
      (node (ref "MQ15") (pin "3") (pinfunction "3_3") (pintype "input"))
      (node (ref "R10") (pin "1") (pinfunction "1_1") (pintype "input"))
      (node (ref "R11") (pin "1") (pinfunction "1_1") (pintype "unspecified"))
      (node (ref "U6") (pin "10") (pinfunction "A5/SPI1_SCK_10") (pintype "bidirectional"))
    )
    (net (code "42") (name "PA6") (class "Default")
      (node (ref "MQ135") (pin "3") (pinfunction "3_3") (pintype "input"))
      (node (ref "U6") (pin "11") (pinfunction "A6/SPI1-MISO_11") (pintype "bidirectional"))
    )
    (net (code "43") (name "PA7") (class "Default")
      (node (ref "MQ2") (pin "3") (pinfunction "3_3") (pintype "input"))
      (node (ref "U6") (pin "12") (pinfunction "A7/SPI1-MOSI_12") (pintype "bidirectional"))
    )
    (net (code "44") (name "PA8") (class "Default")
      (node (ref "R16") (pin "1") (pinfunction "1_1") (pintype "unspecified"))
      (node (ref "U6") (pin "25") (pinfunction "PA8_25") (pintype "bidirectional"))
    )
    (net (code "45") (name "PA9{slash}TX") (class "Default")
      (node (ref "DOWNLOAD1") (pin "4") (pinfunction "4_4") (pintype "unspecified"))
      (node (ref "U6") (pin "26") (pinfunction "PA9/TX1_26") (pintype "bidirectional"))
    )
    (net (code "46") (name "PA10{slash}RX") (class "Default")
      (node (ref "DOWNLOAD1") (pin "3") (pinfunction "3_3") (pintype "unspecified"))
      (node (ref "U6") (pin "27") (pinfunction "A10/RX1_27") (pintype "bidirectional"))
    )
    (net (code "47") (name "PA11") (class "Default")
      (node (ref "R20") (pin "1") (pinfunction "1_1") (pintype "unspecified"))
      (node (ref "U6") (pin "28") (pinfunction "A11_28") (pintype "bidirectional"))
    )
    (net (code "48") (name "PA12") (class "Default")
      (node (ref "R5") (pin "1") (pinfunction "1_1") (pintype "unspecified"))
      (node (ref "U6") (pin "29") (pinfunction "A12_29") (pintype "bidirectional"))
    )
    (net (code "49") (name "PB0") (class "Default")
      (node (ref "R30") (pin "2") (pinfunction "2_2") (pintype "unspecified"))
      (node (ref "SW2") (pin "3") (pinfunction "3_3") (pintype "unspecified"))
      (node (ref "SW2") (pin "4") (pinfunction "4_4") (pintype "unspecified"))
      (node (ref "U6") (pin "13") (pinfunction "B0/ADC8_13") (pintype "bidirectional"))
    )
    (net (code "50") (name "PB1") (class "Default")
      (node (ref "R14") (pin "2") (pinfunction "2_2") (pintype "unspecified"))
      (node (ref "SW3") (pin "3") (pinfunction "3_3") (pintype "unspecified"))
      (node (ref "SW3") (pin "4") (pinfunction "4_4") (pintype "unspecified"))
      (node (ref "U6") (pin "14") (pinfunction "B1/ADC9_14") (pintype "bidirectional"))
    )
    (net (code "51") (name "PB3{slash}DATA") (class "Default")
      (node (ref "HX711") (pin "2") (pinfunction "2_2") (pintype "unspecified"))
      (node (ref "U6") (pin "31") (pinfunction "B3/JTDO_31") (pintype "bidirectional"))
    )
    (net (code "52") (name "PB4{slash}CLK") (class "Default")
      (node (ref "HX711") (pin "3") (pinfunction "3_3") (pintype "unspecified"))
      (node (ref "U6") (pin "32") (pinfunction "B4/JNTRST_32") (pintype "bidirectional"))
    )
    (net (code "53") (name "PB5{slash}SCL") (class "Default")
      (node (ref "OLED1") (pin "3") (pinfunction "SCL_3") (pintype "unspecified"))
      (node (ref "U6") (pin "33") (pinfunction "B5_33") (pintype "bidirectional"))
    )
    (net (code "54") (name "PB6{slash}SDA") (class "Default")
      (node (ref "OLED1") (pin "4") (pinfunction "SDA_4") (pintype "unspecified"))
      (node (ref "U6") (pin "34") (pinfunction "B6/I2C1-SCL_34") (pintype "bidirectional"))
    )
    (net (code "55") (name "PB7") (class "Default")
      (node (ref "H2") (pin "1") (pinfunction "1_1") (pintype "input"))
      (node (ref "U6") (pin "35") (pinfunction "B7/I2C1-SDA_35") (pintype "bidirectional"))
    )
    (net (code "56") (name "PB8") (class "Default")
      (node (ref "R21") (pin "1") (pinfunction "1_1") (pintype "unspecified"))
      (node (ref "U6") (pin "36") (pinfunction "B8_36") (pintype "bidirectional"))
    )
    (net (code "57") (name "PB9{slash}ADDR") (class "Default")
      (node (ref "R1") (pin "1") (pinfunction "1_1") (pintype "unspecified"))
      (node (ref "R13") (pin "2") (pinfunction "2_2") (pintype "unspecified"))
      (node (ref "U6") (pin "37") (pinfunction "B9_37") (pintype "bidirectional"))
      (node (ref "ULN2003") (pin "4") (pinfunction "IN4_4") (pintype "unspecified"))
    )
    (net (code "58") (name "PB10") (class "Default")
      (node (ref "R25") (pin "2") (pinfunction "2_2") (pintype "unspecified"))
      (node (ref "SW5") (pin "3") (pinfunction "3_3") (pintype "unspecified"))
      (node (ref "SW5") (pin "4") (pinfunction "4_4") (pintype "unspecified"))
      (node (ref "U6") (pin "15") (pinfunction "B10/TX3_15") (pintype "bidirectional"))
    )
    (net (code "59") (name "PB11") (class "Default")
      (node (ref "DHT11") (pin "2") (pinfunction "2_2") (pintype "input"))
      (node (ref "R7") (pin "1") (pinfunction "1_1") (pintype "unspecified"))
      (node (ref "U6") (pin "16") (pinfunction "B11/RX3_16") (pintype "bidirectional"))
    )
    (net (code "60") (name "PB12") (class "Default")
      (node (ref "R31") (pin "2") (pinfunction "2_2") (pintype "unspecified"))
      (node (ref "SW4") (pin "3") (pinfunction "3_3") (pintype "unspecified"))
      (node (ref "SW4") (pin "4") (pinfunction "4_4") (pintype "unspecified"))
      (node (ref "U6") (pin "21") (pinfunction "B12_21") (pintype "bidirectional"))
    )
    (net (code "61") (name "PC13") (class "Default")
      (node (ref "H1") (pin "1") (pinfunction "1_1") (pintype "input"))
      (node (ref "U6") (pin "2") (pinfunction "C13_2") (pintype "bidirectional"))
    )
    (net (code "62") (name "PC14") (class "Default")
      (node (ref "R12") (pin "1") (pinfunction "1_1") (pintype "unspecified"))
      (node (ref "U6") (pin "3") (pinfunction "C14_3") (pintype "bidirectional"))
      (node (ref "ULN2003") (pin "2") (pinfunction "IN2_2") (pintype "unspecified"))
    )
    (net (code "63") (name "PC15") (class "Default")
      (node (ref "R2") (pin "1") (pinfunction "1_1") (pintype "unspecified"))
      (node (ref "U6") (pin "4") (pinfunction "C15_4") (pintype "bidirectional"))
      (node (ref "ULN2003") (pin "3") (pinfunction "IN3_3") (pintype "unspecified"))
    )
    (net (code "64") (name "unconnected-(ESP8266-IO0-Pad3)") (class "Default")
      (node (ref "ESP8266") (pin "3") (pinfunction "IO0_3") (pintype "unspecified+no_connect"))
    )
    (net (code "65") (name "unconnected-(ESP8266-IO2-Pad2)") (class "Default")
      (node (ref "ESP8266") (pin "2") (pinfunction "IO2_2") (pintype "unspecified+no_connect"))
    )
    (net (code "66") (name "unconnected-(H3-Pad1)") (class "Default")
      (node (ref "H3") (pin "1") (pinfunction "1_1") (pintype "input+no_connect"))
    )
    (net (code "67") (name "unconnected-(H3-Pad6)") (class "Default")
      (node (ref "H3") (pin "6") (pinfunction "6_6") (pintype "input+no_connect"))
    )
    (net (code "68") (name "unconnected-(K1-Pad3)") (class "Default")
      (node (ref "K1") (pin "3") (pinfunction "3_3") (pintype "input+no_connect"))
    )
    (net (code "69") (name "unconnected-(K2-Pad3)") (class "Default")
      (node (ref "K2") (pin "3") (pinfunction "3_3") (pintype "input+no_connect"))
    )
    (net (code "70") (name "unconnected-(K3-Pad3)") (class "Default")
      (node (ref "K3") (pin "3") (pinfunction "3_3") (pintype "input+no_connect"))
    )
    (net (code "71") (name "unconnected-(U6-A15{slash}JTDI-Pad30)") (class "Default")
      (node (ref "U6") (pin "30") (pinfunction "A15/JTDI_30") (pintype "bidirectional+no_connect"))
    )
    (net (code "72") (name "unconnected-(U6-B13-Pad22)") (class "Default")
      (node (ref "U6") (pin "22") (pinfunction "B13_22") (pintype "bidirectional+no_connect"))
    )
    (net (code "73") (name "unconnected-(U6-B14-Pad23)") (class "Default")
      (node (ref "U6") (pin "23") (pinfunction "B14_23") (pintype "bidirectional+no_connect"))
    )
    (net (code "74") (name "unconnected-(U6-B15-Pad24)") (class "Default")
      (node (ref "U6") (pin "24") (pinfunction "B15_24") (pintype "bidirectional+no_connect"))
    )
    (net (code "75") (name "unconnected-(U6-RST-Pad17)") (class "Default")
      (node (ref "U6") (pin "17") (pinfunction "RST_17") (pintype "bidirectional+no_connect"))
    )
    (net (code "76") (name "unconnected-(U6-VB-Pad1)") (class "Default")
      (node (ref "U6") (pin "1") (pinfunction "VB_1") (pintype "unspecified+no_connect"))
    )
    (net (code "77") (name "unconnected-(USB1-D+-Pad3)") (class "Default")
      (node (ref "USB1") (pin "3") (pinfunction "D+_3") (pintype "input+no_connect"))
    )
    (net (code "78") (name "unconnected-(USB1-D--Pad2)") (class "Default")
      (node (ref "USB1") (pin "2") (pinfunction "D-_2") (pintype "input+no_connect"))
    )
  )
)
